# OpenSprinkler_v14_smt.net
KiCad netlist of a schematic drawn in EAGLE
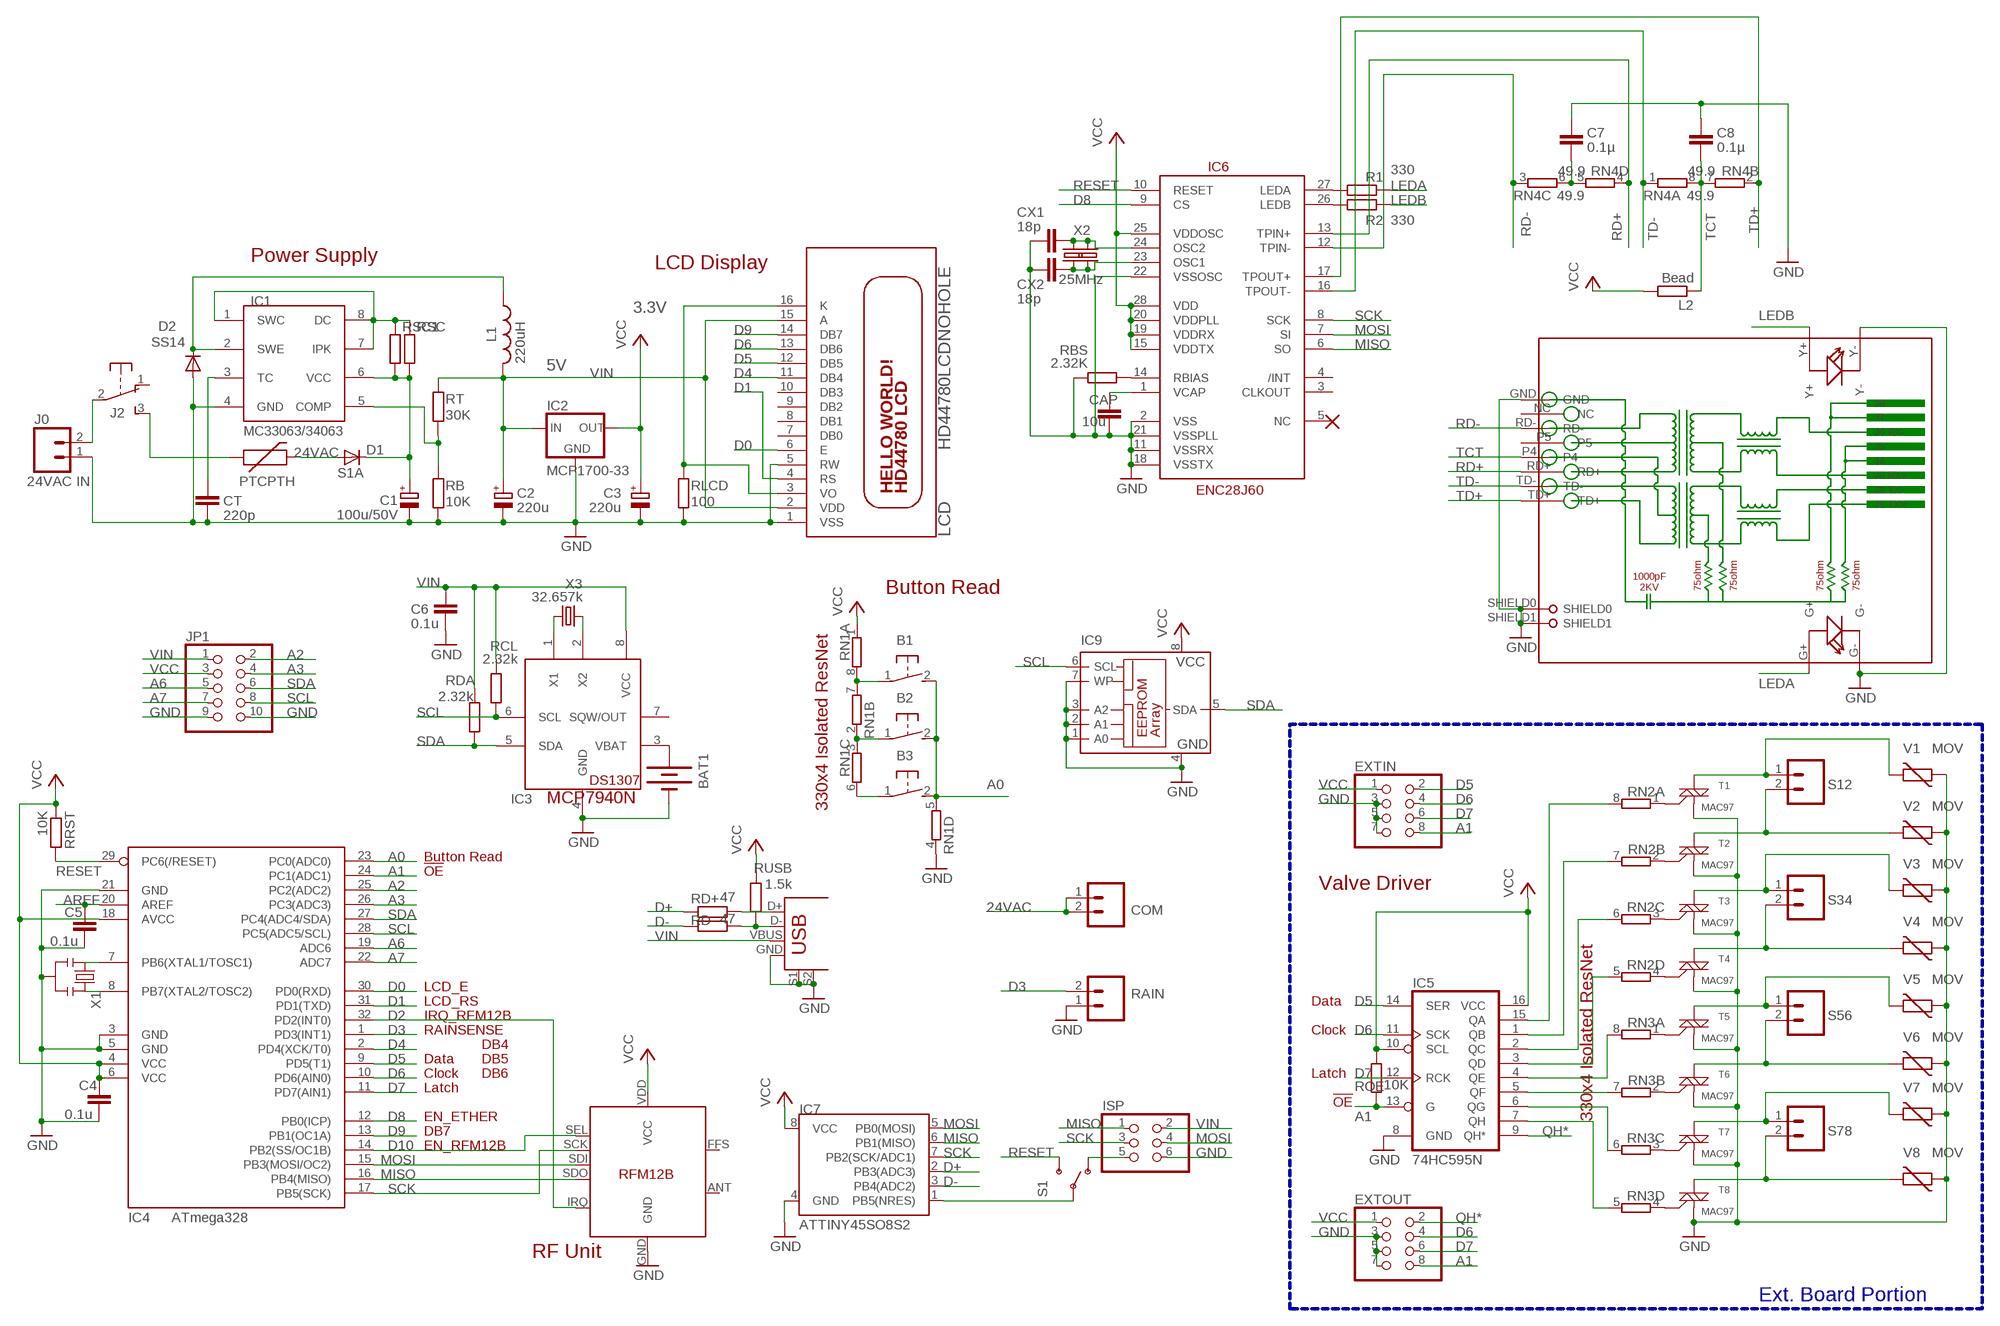
[diagram p0: schematic, sheet 1]

(export (version "E")
  (design (tool "Eeschema 10.0.6"))
  (components
    (comp (ref "B1")
      (value "31-XX")
      (footprint "eagle-import:B3F-31XX")
      (libsource (lib "eagle-import") (part "31-XX"))
    )
    (comp (ref "B2")
      (value "31-XX")
      (footprint "eagle-import:B3F-31XX")
      (libsource (lib "eagle-import") (part "31-XX"))
    )
    (comp (ref "B3")
      (value "31-XX")
      (footprint "eagle-import:B3F-31XX")
      (libsource (lib "eagle-import") (part "31-XX"))
    )
    (comp (ref "BAT1")
      (value "BATTERY12PTH")
      (footprint "eagle-import:BATTCON_12MM_PTH")
      (libsource (lib "eagle-import") (part "BATTERY12PTH"))
    )
    (comp (ref "C1")
      (value "100u/50V")
      (footprint "eagle-import:E3,5-8")
      (libsource (lib "eagle-import") (part "CPOL-EUE3.5-8"))
    )
    (comp (ref "C2")
      (value "220u")
      (footprint "eagle-import:E2-5")
      (libsource (lib "eagle-import") (part "CPOL-EUE2-5"))
    )
    (comp (ref "C3")
      (value "220u")
      (footprint "eagle-import:E2-5")
      (libsource (lib "eagle-import") (part "CPOL-EUE2-5"))
    )
    (comp (ref "C4")
      (value "0.1u")
      (footprint "eagle-import:C0805")
      (libsource (lib "eagle-import") (part "C-EUC0805"))
    )
    (comp (ref "C5")
      (value "0.1u")
      (footprint "eagle-import:C0805")
      (libsource (lib "eagle-import") (part "C-EUC0805"))
    )
    (comp (ref "C6")
      (value "0.1u")
      (footprint "eagle-import:C0805")
      (libsource (lib "eagle-import") (part "C-EUC0805"))
    )
    (comp (ref "C7")
      (value "0.1µ")
      (footprint "eagle-import:C0805")
      (libsource (lib "eagle-import") (part "resistor_C-EUC0805"))
    )
    (comp (ref "C8")
      (value "0.1µ")
      (footprint "eagle-import:C0805")
      (libsource (lib "eagle-import") (part "resistor_C-EUC0805"))
    )
    (comp (ref "CAP")
      (value "10u")
      (footprint "eagle-import:C0805")
      (libsource (lib "eagle-import") (part "resistor_C-EUC0805"))
    )
    (comp (ref "COM")
      (value "M025MM")
      (footprint "eagle-import:SCREWTERMINAL-5MM-2")
      (libsource (lib "eagle-import") (part "M025MM"))
    )
    (comp (ref "CT")
      (value "220p")
      (footprint "eagle-import:C0805")
      (libsource (lib "eagle-import") (part "C-EUC0805"))
    )
    (comp (ref "CX1")
      (value "18p")
      (footprint "eagle-import:C0805")
      (libsource (lib "eagle-import") (part "resistor_C-EUC0805"))
    )
    (comp (ref "CX2")
      (value "18p")
      (footprint "eagle-import:C0805")
      (libsource (lib "eagle-import") (part "resistor_C-EUC0805"))
    )
    (comp (ref "D1")
      (value "S1A")
      (footprint "eagle-import:DO214AC")
      (libsource (lib "eagle-import") (part "DIODE-DO214AC"))
    )
    (comp (ref "D2")
      (value "SS14")
      (footprint "eagle-import:DO214AC")
      (libsource (lib "eagle-import") (part "DIODE-DO214AC"))
    )
    (comp (ref "EXTIN")
      (value "PINHD-2X4")
      (footprint "eagle-import:2X04")
      (libsource (lib "eagle-import") (part "PINHD-2X4"))
    )
    (comp (ref "EXTOUT")
      (value "PINHD-2X4")
      (footprint "eagle-import:2X04")
      (libsource (lib "eagle-import") (part "PINHD-2X4"))
    )
    (comp (ref "IC1")
      (value "MC33063/MC34063D")
      (footprint "eagle-import:SO08")
      (libsource (lib "eagle-import") (part "MC33063/MC34063D"))
    )
    (comp (ref "IC2")
      (value "MCP1700-33")
      (footprint "eagle-import:SOT23")
      (libsource (lib "eagle-import") (part "MCP1700SOT233"))
    )
    (comp (ref "IC3")
      (value "MCP7940N")
      (footprint "eagle-import:SO08")
      (libsource (lib "eagle-import") (part "DS1307SOIC"))
    )
    (comp (ref "IC4")
      (value "ATmega328")
      (footprint "eagle-import:TQFP32-08")
      (fields (field (name "MPN") "ATMEGA8-16AU"))
      (libsource (lib "eagle-import") (part "MEGA8-AI"))
    )
    (comp (ref "IC5")
      (value "74HC595N")
      (footprint "eagle-import:SO16")
      (libsource (lib "eagle-import") (part "74595DLS"))
    )
    (comp (ref "IC6")
      (value "ENC28J60")
      (footprint "eagle-import:SOIC28WLONG")
      (libsource (lib "eagle-import") (part "ENC28J60SO28LONG"))
    )
    (comp (ref "IC7")
      (value "ATTINY45SO8S2")
      (footprint "eagle-import:SO8S2")
      (libsource (lib "eagle-import") (part "ATTINY45SO8S2"))
    )
    (comp (ref "IC8")
      (value "RFM12B")
      (footprint "eagle-import:RFM12B")
      (libsource (lib "eagle-import") (part "RFM12B"))
    )
    (comp (ref "IC9")
      (value "24AA128SN")
      (footprint "eagle-import:SO-08")
      (libsource (lib "eagle-import") (part "24SNAA128"))
    )
    (comp (ref "ISP")
      (value "PINHD-2X3")
      (footprint "eagle-import:2X03")
      (libsource (lib "eagle-import") (part "PINHD-2X3"))
    )
    (comp (ref "J0")
      (value "24VAC IN")
      (footprint "eagle-import:SCREWTERMINAL-5MM-2")
      (libsource (lib "eagle-import") (part "M025MM"))
    )
    (comp (ref "J2")
      (value "EG1206")
      (footprint "eagle-import:EG1206")
      (libsource (lib "eagle-import") (part "EG1206"))
    )
    (comp (ref "JP1")
      (value "PINHD-2X5")
      (footprint "eagle-import:2X05")
      (libsource (lib "eagle-import") (part "PINHD-2X5"))
    )
    (comp (ref "L1")
      (value "220uH")
      (footprint "eagle-import:6000-XXXX-RC")
      (libsource (lib "eagle-import") (part "L-US6000-XXX-RC"))
    )
    (comp (ref "L2")
      (value "Bead")
      (footprint "eagle-import:R0805")
      (libsource (lib "eagle-import") (part "R-EU_R0805"))
    )
    (comp (ref "LCD")
      (value "HD44780LCDNOHOLE")
      (footprint "eagle-import:LCD1602A")
      (libsource (lib "eagle-import") (part "HD44780LCDNOHOLE"))
    )
    (comp (ref "PTC")
      (value "PTCPTH")
      (footprint "eagle-import:PTC")
      (libsource (lib "eagle-import") (part "PTCPTH"))
    )
    (comp (ref "R1")
      (value "330")
      (footprint "eagle-import:R0805")
      (libsource (lib "eagle-import") (part "R-EU_R0805"))
    )
    (comp (ref "R2")
      (value "330")
      (footprint "eagle-import:R0805")
      (libsource (lib "eagle-import") (part "R-EU_R0805"))
    )
    (comp (ref "RAIN")
      (value "M025MM")
      (footprint "eagle-import:SCREWTERMINAL-5MM-2")
      (libsource (lib "eagle-import") (part "M025MM"))
    )
    (comp (ref "RB")
      (value "10K")
      (footprint "eagle-import:R0805")
      (libsource (lib "eagle-import") (part "R-EU_R0805"))
    )
    (comp (ref "RBS")
      (value "2.32K")
      (footprint "eagle-import:R0805")
      (libsource (lib "eagle-import") (part "R-EU_R0805"))
    )
    (comp (ref "RCL")
      (value "2.32k")
      (footprint "eagle-import:R0805")
      (libsource (lib "eagle-import") (part "R-EU_R0805"))
    )
    (comp (ref "RD+")
      (value "47")
      (footprint "eagle-import:R0805")
      (libsource (lib "eagle-import") (part "R-EU_R0805"))
    )
    (comp (ref "RD-")
      (value "47")
      (footprint "eagle-import:R0805")
      (libsource (lib "eagle-import") (part "R-EU_R0805"))
    )
    (comp (ref "RDA")
      (value "2.32k")
      (footprint "eagle-import:R0805")
      (libsource (lib "eagle-import") (part "R-EU_R0805"))
    )
    (comp (ref "RJ1")
      (value "HR911105A")
      (footprint "eagle-import:HR911105A")
      (libsource (lib "eagle-import") (part "HR911105A"))
    )
    (comp (ref "RLCD")
      (value "100")
      (footprint "eagle-import:R0805")
      (libsource (lib "eagle-import") (part "R-EU_R0805"))
    )
    (comp (ref "RN1")
      (value "4R-NEXBV8V")
      (footprint "eagle-import:EXBV8V")
      (libsource (lib "eagle-import") (part "4R-NEXBV8V"))
    )
    (comp (ref "RN2")
      (value "4R-NEXBV8V")
      (footprint "eagle-import:EXBV8V")
      (libsource (lib "eagle-import") (part "4R-NEXBV8V"))
    )
    (comp (ref "RN3")
      (value "4R-NEXBV8V")
      (footprint "eagle-import:EXBV8V")
      (libsource (lib "eagle-import") (part "4R-NEXBV8V"))
    )
    (comp (ref "RN4")
      (value "49.9")
      (footprint "eagle-import:EXBV8V")
      (libsource (lib "eagle-import") (part "4R-NEXBV8V"))
    )
    (comp (ref "ROE")
      (value "10K")
      (footprint "eagle-import:R0805")
      (libsource (lib "eagle-import") (part "R-EU_R0805"))
    )
    (comp (ref "RRST")
      (value "10K")
      (footprint "eagle-import:R0805")
      (libsource (lib "eagle-import") (part "R-EU_R0805"))
    )
    (comp (ref "RSC")
      (value "1.0")
      (footprint "eagle-import:R0805")
      (libsource (lib "eagle-import") (part "R-EU_R0805"))
    )
    (comp (ref "RSC1")
      (value "1.0")
      (footprint "eagle-import:R0805")
      (libsource (lib "eagle-import") (part "R-EU_R0805"))
    )
    (comp (ref "RT")
      (value "30K")
      (footprint "eagle-import:R0805")
      (libsource (lib "eagle-import") (part "R-EU_R0805"))
    )
    (comp (ref "RUSB")
      (value "1.5k")
      (footprint "eagle-import:R0805")
      (libsource (lib "eagle-import") (part "R-EU_R0805"))
    )
    (comp (ref "S1")
      (value "SWITCH-SPSTSMD2")
      (footprint "eagle-import:SWITCH-SPDT-SMD")
      (libsource (lib "eagle-import") (part "SWITCH-SPSTSMD2"))
    )
    (comp (ref "S12")
      (value "M025MM")
      (footprint "eagle-import:SCREWTERMINAL-5MM-2")
      (libsource (lib "eagle-import") (part "M025MM"))
    )
    (comp (ref "S34")
      (value "M025MM")
      (footprint "eagle-import:SCREWTERMINAL-5MM-2")
      (libsource (lib "eagle-import") (part "M025MM"))
    )
    (comp (ref "S56")
      (value "M025MM")
      (footprint "eagle-import:SCREWTERMINAL-5MM-2")
      (libsource (lib "eagle-import") (part "M025MM"))
    )
    (comp (ref "S78")
      (value "M025MM")
      (footprint "eagle-import:SCREWTERMINAL-5MM-2")
      (libsource (lib "eagle-import") (part "M025MM"))
    )
    (comp (ref "T1")
      (value "MAC97")
      (footprint "eagle-import:SOT223")
      (libsource (lib "eagle-import") (part "MAC97SOT223"))
    )
    (comp (ref "T2")
      (value "MAC97")
      (footprint "eagle-import:SOT223")
      (libsource (lib "eagle-import") (part "MAC97SOT223"))
    )
    (comp (ref "T3")
      (value "MAC97")
      (footprint "eagle-import:SOT223")
      (libsource (lib "eagle-import") (part "MAC97SOT223"))
    )
    (comp (ref "T4")
      (value "MAC97")
      (footprint "eagle-import:SOT223")
      (libsource (lib "eagle-import") (part "MAC97SOT223"))
    )
    (comp (ref "T5")
      (value "MAC97")
      (footprint "eagle-import:SOT223")
      (libsource (lib "eagle-import") (part "MAC97SOT223"))
    )
    (comp (ref "T6")
      (value "MAC97")
      (footprint "eagle-import:SOT223")
      (libsource (lib "eagle-import") (part "MAC97SOT223"))
    )
    (comp (ref "T7")
      (value "MAC97")
      (footprint "eagle-import:SOT223")
      (libsource (lib "eagle-import") (part "MAC97SOT223"))
    )
    (comp (ref "T8")
      (value "MAC97")
      (footprint "eagle-import:SOT223")
      (libsource (lib "eagle-import") (part "MAC97SOT223"))
    )
    (comp (ref "USB")
      (value "USB+SHIELD")
      (footprint "eagle-import:USB-B-PTH")
      (libsource (lib "eagle-import") (part "USB+SHIELD"))
    )
    (comp (ref "V1")
      (value "MOV")
      (footprint "eagle-import:R-5")
      (libsource (lib "eagle-import") (part "VARISTOR-5"))
    )
    (comp (ref "V2")
      (value "MOV")
      (footprint "eagle-import:R-5")
      (libsource (lib "eagle-import") (part "VARISTOR-5"))
    )
    (comp (ref "V3")
      (value "MOV")
      (footprint "eagle-import:R-5")
      (libsource (lib "eagle-import") (part "VARISTOR-5"))
    )
    (comp (ref "V4")
      (value "MOV")
      (footprint "eagle-import:R-5")
      (libsource (lib "eagle-import") (part "VARISTOR-5"))
    )
    (comp (ref "V5")
      (value "MOV")
      (footprint "eagle-import:R-5")
      (libsource (lib "eagle-import") (part "VARISTOR-5"))
    )
    (comp (ref "V6")
      (value "MOV")
      (footprint "eagle-import:R-5")
      (libsource (lib "eagle-import") (part "VARISTOR-5"))
    )
    (comp (ref "V7")
      (value "MOV")
      (footprint "eagle-import:R-5")
      (libsource (lib "eagle-import") (part "VARISTOR-5"))
    )
    (comp (ref "V8")
      (value "MOV")
      (footprint "eagle-import:R-5")
      (libsource (lib "eagle-import") (part "VARISTOR-5"))
    )
    (comp (ref "X1")
      (value "RESONATORSMD")
      (footprint "eagle-import:RESONATOR-SMD")
      (libsource (lib "eagle-import") (part "RESONATORSMD"))
    )
    (comp (ref "X2")
      (value "25MHz")
      (footprint "eagle-import:HC49UP")
      (libsource (lib "eagle-import") (part "CRYSTALSMD"))
    )
    (comp (ref "X2A")
      (value "25MHz")
      (footprint "eagle-import:HC49US")
      (libsource (lib "eagle-import") (part "CRYSTALHC49US"))
    )
    (comp (ref "X3")
      (value "32.657k")
      (footprint "eagle-import:TC26H")
      (libsource (lib "eagle-import") (part "crystal_CRYSTALTC26H"))
    )
  )
  (nets
    (net (code "1") (name "/24VAC") (class "Default")
      (node (ref "COM") (pin "1") (pinfunction "1_1") (pintype "passive"))
      (node (ref "COM") (pin "2") (pinfunction "2_2") (pintype "passive"))
      (node (ref "D1") (pin "A") (pinfunction "A_A") (pintype "passive"))
      (node (ref "PTC") (pin "P$2") (pinfunction "2_P$2") (pintype "bidirectional"))
    )
    (net (code "2") (name "/A0") (class "Default")
      (node (ref "B1") (pin "2") (pinfunction "S_2") (pintype "passive"))
      (node (ref "B2") (pin "2") (pinfunction "S_2") (pintype "passive"))
      (node (ref "B3") (pin "2") (pinfunction "S_2") (pintype "passive"))
      (node (ref "IC4") (pin "23") (pinfunction "PC0(ADC0)_23") (pintype "bidirectional"))
      (node (ref "RN1") (pin "5") (pinfunction "2_5") (pintype "passive"))
    )
    (net (code "3") (name "/A1") (class "Default")
      (node (ref "EXTIN") (pin "8") (pinfunction "8_8") (pintype "passive"))
      (node (ref "EXTOUT") (pin "8") (pinfunction "8_8") (pintype "passive"))
      (node (ref "IC4") (pin "24") (pinfunction "PC1(ADC1)_24") (pintype "bidirectional"))
      (node (ref "IC5") (pin "13") (pinfunction "G_13") (pintype "input"))
      (node (ref "ROE") (pin "1") (pinfunction "1_1") (pintype "passive"))
    )
    (net (code "4") (name "/A2") (class "Default")
      (node (ref "IC4") (pin "25") (pinfunction "PC2(ADC2)_25") (pintype "bidirectional"))
      (node (ref "JP1") (pin "2") (pinfunction "2_2") (pintype "passive"))
    )
    (net (code "5") (name "/A3") (class "Default")
      (node (ref "IC4") (pin "26") (pinfunction "PC3(ADC3)_26") (pintype "bidirectional"))
      (node (ref "JP1") (pin "4") (pinfunction "4_4") (pintype "passive"))
    )
    (net (code "6") (name "/A6") (class "Default")
      (node (ref "IC4") (pin "19") (pinfunction "ADC6_19") (pintype "bidirectional"))
      (node (ref "JP1") (pin "5") (pinfunction "5_5") (pintype "passive"))
    )
    (net (code "7") (name "/A7") (class "Default")
      (node (ref "IC4") (pin "22") (pinfunction "ADC7_22") (pintype "bidirectional"))
      (node (ref "JP1") (pin "7") (pinfunction "7_7") (pintype "passive"))
    )
    (net (code "8") (name "/AREF") (class "Default")
      (node (ref "C5") (pin "1") (pinfunction "1_1") (pintype "passive"))
      (node (ref "IC4") (pin "20") (pinfunction "AREF_20") (pintype "passive"))
    )
    (net (code "9") (name "/D+") (class "Default")
      (node (ref "IC7") (pin "2") (pinfunction "PB3(ADC3)_2") (pintype "bidirectional"))
      (node (ref "RD+") (pin "1") (pinfunction "1_1") (pintype "passive"))
    )
    (net (code "10") (name "/D-") (class "Default")
      (node (ref "IC7") (pin "3") (pinfunction "PB4(ADC2)_3") (pintype "bidirectional"))
      (node (ref "RD-") (pin "1") (pinfunction "1_1") (pintype "passive"))
    )
    (net (code "11") (name "/D0") (class "Default")
      (node (ref "IC4") (pin "30") (pinfunction "PD0(RXD)_30") (pintype "bidirectional"))
      (node (ref "LCD") (pin "6") (pinfunction "E_6") (pintype "input"))
    )
    (net (code "12") (name "/D1") (class "Default")
      (node (ref "IC4") (pin "31") (pinfunction "PD1(TXD)_31") (pintype "bidirectional"))
      (node (ref "LCD") (pin "4") (pinfunction "RS_4") (pintype "input"))
    )
    (net (code "13") (name "/D2") (class "Default")
      (node (ref "IC4") (pin "32") (pinfunction "PD2(INT0)_32") (pintype "bidirectional"))
      (node (ref "IC8") (pin "IRQ") (pinfunction "IRQ_IRQ") (pintype "open_collector"))
    )
    (net (code "14") (name "/D3") (class "Default")
      (node (ref "IC4") (pin "1") (pinfunction "PD3(INT1)_1") (pintype "bidirectional"))
      (node (ref "RAIN") (pin "2") (pinfunction "2_2") (pintype "passive"))
    )
    (net (code "15") (name "/D4") (class "Default")
      (node (ref "IC4") (pin "2") (pinfunction "PD4(XCK/T0)_2") (pintype "bidirectional"))
      (node (ref "LCD") (pin "11") (pinfunction "DB4_11") (pintype "bidirectional"))
    )
    (net (code "16") (name "/D5") (class "Default")
      (node (ref "EXTIN") (pin "2") (pinfunction "2_2") (pintype "passive"))
      (node (ref "IC4") (pin "9") (pinfunction "PD5(T1)_9") (pintype "bidirectional"))
      (node (ref "IC5") (pin "14") (pinfunction "SER_14") (pintype "input"))
      (node (ref "LCD") (pin "12") (pinfunction "DB5_12") (pintype "bidirectional"))
    )
    (net (code "17") (name "/D6") (class "Default")
      (node (ref "EXTIN") (pin "4") (pinfunction "4_4") (pintype "passive"))
      (node (ref "EXTOUT") (pin "4") (pinfunction "4_4") (pintype "passive"))
      (node (ref "IC4") (pin "10") (pinfunction "PD6(AIN0)_10") (pintype "bidirectional"))
      (node (ref "IC5") (pin "11") (pinfunction "SCK_11") (pintype "input"))
      (node (ref "LCD") (pin "13") (pinfunction "DB6_13") (pintype "bidirectional"))
    )
    (net (code "18") (name "/D7") (class "Default")
      (node (ref "EXTIN") (pin "6") (pinfunction "6_6") (pintype "passive"))
      (node (ref "EXTOUT") (pin "6") (pinfunction "6_6") (pintype "passive"))
      (node (ref "IC4") (pin "11") (pinfunction "PD7(AIN1)_11") (pintype "bidirectional"))
      (node (ref "IC5") (pin "12") (pinfunction "RCK_12") (pintype "input"))
    )
    (net (code "19") (name "/D8") (class "Default")
      (node (ref "IC4") (pin "12") (pinfunction "PB0(ICP)_12") (pintype "bidirectional"))
      (node (ref "IC6") (pin "9") (pinfunction "CS_9") (pintype "bidirectional"))
    )
    (net (code "20") (name "/D9") (class "Default")
      (node (ref "IC4") (pin "13") (pinfunction "PB1(OC1A)_13") (pintype "bidirectional"))
      (node (ref "LCD") (pin "14") (pinfunction "DB7_14") (pintype "bidirectional"))
    )
    (net (code "21") (name "/D10") (class "Default")
      (node (ref "IC4") (pin "14") (pinfunction "PB2(SS/OC1B)_14") (pintype "bidirectional"))
      (node (ref "IC8") (pin "SEL") (pinfunction "SEL_SEL") (pintype "input"))
    )
    (net (code "22") (name "/LEDA") (class "Default")
      (node (ref "R1") (pin "2") (pinfunction "2_2") (pintype "passive"))
      (node (ref "RJ1") (pin "G+") (pinfunction "G+_G+") (pintype "bidirectional"))
    )
    (net (code "23") (name "/LEDB") (class "Default")
      (node (ref "R2") (pin "2") (pinfunction "2_2") (pintype "passive"))
      (node (ref "RJ1") (pin "Y+") (pinfunction "Y+_Y+") (pintype "bidirectional"))
    )
    (net (code "24") (name "/MISO") (class "Default")
      (node (ref "IC4") (pin "16") (pinfunction "PB4(MISO)_16") (pintype "bidirectional"))
      (node (ref "IC6") (pin "6") (pinfunction "SO_6") (pintype "bidirectional"))
      (node (ref "IC7") (pin "6") (pinfunction "PB1(MISO)_6") (pintype "bidirectional"))
      (node (ref "IC8") (pin "SDO") (pinfunction "SDO_SDO") (pintype "output"))
      (node (ref "ISP") (pin "1") (pinfunction "1_1") (pintype "passive"))
    )
    (net (code "25") (name "/MOSI") (class "Default")
      (node (ref "IC4") (pin "15") (pinfunction "PB3(MOSI/OC2)_15") (pintype "bidirectional"))
      (node (ref "IC6") (pin "7") (pinfunction "SI_7") (pintype "bidirectional"))
      (node (ref "IC7") (pin "5") (pinfunction "PB0(MOSI)_5") (pintype "bidirectional"))
      (node (ref "IC8") (pin "SDI") (pinfunction "SDI_SDI") (pintype "input"))
      (node (ref "ISP") (pin "4") (pinfunction "4_4") (pintype "passive"))
    )
    (net (code "26") (name "/QH*") (class "Default")
      (node (ref "EXTOUT") (pin "2") (pinfunction "2_2") (pintype "passive"))
      (node (ref "IC5") (pin "9") (pinfunction "QH*_9") (pintype "tri_state"))
    )
    (net (code "27") (name "/RD+") (class "Default")
      (node (ref "IC6") (pin "13") (pinfunction "TPIN+_13") (pintype "bidirectional"))
      (node (ref "RJ1") (pin "RD+") (pinfunction "RD+_RD+") (pintype "bidirectional"))
      (node (ref "RN4") (pin "4") (pinfunction "1_4") (pintype "passive"))
    )
    (net (code "28") (name "/RD-") (class "Default")
      (node (ref "IC6") (pin "12") (pinfunction "TPIN-_12") (pintype "bidirectional"))
      (node (ref "RJ1") (pin "RD-") (pinfunction "RD-_RD-") (pintype "bidirectional"))
      (node (ref "RN4") (pin "3") (pinfunction "1_3") (pintype "passive"))
    )
    (net (code "29") (name "/RESET") (class "Default")
      (node (ref "IC4") (pin "29") (pinfunction "PC6(/RESET)_29") (pintype "bidirectional"))
      (node (ref "IC6") (pin "10") (pinfunction "RESET_10") (pintype "bidirectional"))
      (node (ref "RRST") (pin "2") (pinfunction "2_2") (pintype "passive"))
      (node (ref "S1") (pin "3") (pinfunction "S_3") (pintype "passive"))
    )
    (net (code "30") (name "/SCK") (class "Default")
      (node (ref "IC4") (pin "17") (pinfunction "PB5(SCK)_17") (pintype "bidirectional"))
      (node (ref "IC6") (pin "8") (pinfunction "SCK_8") (pintype "bidirectional"))
      (node (ref "IC7") (pin "7") (pinfunction "PB2(SCK/ADC1)_7") (pintype "bidirectional"))
      (node (ref "IC8") (pin "SCK") (pinfunction "SCK_SCK") (pintype "input"))
      (node (ref "ISP") (pin "3") (pinfunction "3_3") (pintype "passive"))
    )
    (net (code "31") (name "/SCL") (class "Default")
      (node (ref "IC3") (pin "6") (pinfunction "SCL_6") (pintype "bidirectional"))
      (node (ref "IC4") (pin "28") (pinfunction "PC5(ADC5/SCL)_28") (pintype "bidirectional"))
      (node (ref "IC9") (pin "6") (pinfunction "SCL_6") (pintype "input"))
      (node (ref "JP1") (pin "8") (pinfunction "8_8") (pintype "passive"))
      (node (ref "RCL") (pin "2") (pinfunction "2_2") (pintype "passive"))
    )
    (net (code "32") (name "/SDA") (class "Default")
      (node (ref "IC3") (pin "5") (pinfunction "SDA_5") (pintype "bidirectional"))
      (node (ref "IC4") (pin "27") (pinfunction "PC4(ADC4/SDA)_27") (pintype "bidirectional"))
      (node (ref "IC9") (pin "5") (pinfunction "SDA_5") (pintype "bidirectional"))
      (node (ref "JP1") (pin "6") (pinfunction "6_6") (pintype "passive"))
      (node (ref "RDA") (pin "2") (pinfunction "2_2") (pintype "passive"))
    )
    (net (code "33") (name "/TCT") (class "Default")
      (node (ref "C8") (pin "2") (pinfunction "2_2") (pintype "passive"))
      (node (ref "L2") (pin "1") (pinfunction "1_1") (pintype "passive"))
      (node (ref "RJ1") (pin "P4") (pinfunction "P4_P4") (pintype "bidirectional"))
      (node (ref "RN4") (pin "7") (pinfunction "2_7") (pintype "passive"))
      (node (ref "RN4") (pin "8") (pinfunction "2_8") (pintype "passive"))
    )
    (net (code "34") (name "/TD+") (class "Default")
      (node (ref "IC6") (pin "17") (pinfunction "TPOUT+_17") (pintype "bidirectional"))
      (node (ref "RJ1") (pin "TD+") (pinfunction "TD+_TD+") (pintype "bidirectional"))
      (node (ref "RN4") (pin "2") (pinfunction "1_2") (pintype "passive"))
    )
    (net (code "35") (name "/TD-") (class "Default")
      (node (ref "IC6") (pin "16") (pinfunction "TPOUT-_16") (pintype "bidirectional"))
      (node (ref "RJ1") (pin "TD-") (pinfunction "TD-_TD-") (pintype "bidirectional"))
      (node (ref "RN4") (pin "1") (pinfunction "1_1") (pintype "passive"))
    )
    (net (code "36") (name "/VIN") (class "Default")
      (node (ref "C2") (pin "+") (pinfunction "+_+") (pintype "passive"))
      (node (ref "C6") (pin "1") (pinfunction "1_1") (pintype "passive"))
      (node (ref "IC2") (pin "3") (pinfunction "IN_3") (pintype "input"))
      (node (ref "IC3") (pin "8") (pinfunction "VCC_8") (pintype "power_in"))
      (node (ref "ISP") (pin "2") (pinfunction "2_2") (pintype "passive"))
      (node (ref "JP1") (pin "1") (pinfunction "1_1") (pintype "passive"))
      (node (ref "L1") (pin "2") (pinfunction "2_2") (pintype "passive"))
      (node (ref "LCD") (pin "15") (pinfunction "A_15") (pintype "input"))
      (node (ref "LCD") (pin "2") (pinfunction "VDD_2") (pintype "power_in"))
      (node (ref "RCL") (pin "1") (pinfunction "1_1") (pintype "passive"))
      (node (ref "RDA") (pin "1") (pinfunction "1_1") (pintype "passive"))
      (node (ref "RT") (pin "1") (pinfunction "1_1") (pintype "passive"))
      (node (ref "USB") (pin "VBUS") (pinfunction "VBUS_VBUS") (pintype "bidirectional"))
    )
    (net (code "37") (name "GND") (class "Default")
      (node (ref "BAT1") (pin "GND") (pinfunction "-_GND") (pintype "power_in"))
      (node (ref "C1") (pin "-") (pinfunction "-_-") (pintype "passive"))
      (node (ref "C2") (pin "-") (pinfunction "-_-") (pintype "passive"))
      (node (ref "C3") (pin "-") (pinfunction "-_-") (pintype "passive"))
      (node (ref "C4") (pin "2") (pinfunction "2_2") (pintype "passive"))
      (node (ref "C5") (pin "2") (pinfunction "2_2") (pintype "passive"))
      (node (ref "C6") (pin "2") (pinfunction "2_2") (pintype "passive"))
      (node (ref "C7") (pin "1") (pinfunction "1_1") (pintype "passive"))
      (node (ref "C8") (pin "1") (pinfunction "1_1") (pintype "passive"))
      (node (ref "CAP") (pin "2") (pinfunction "2_2") (pintype "passive"))
      (node (ref "CT") (pin "2") (pinfunction "2_2") (pintype "passive"))
      (node (ref "CX1") (pin "2") (pinfunction "2_2") (pintype "passive"))
      (node (ref "CX2") (pin "2") (pinfunction "2_2") (pintype "passive"))
      (node (ref "D2") (pin "A") (pinfunction "A_A") (pintype "passive"))
      (node (ref "EXTIN") (pin "3") (pinfunction "3_3") (pintype "passive"))
      (node (ref "EXTIN") (pin "5") (pinfunction "5_5") (pintype "passive"))
      (node (ref "EXTIN") (pin "7") (pinfunction "7_7") (pintype "passive"))
      (node (ref "EXTOUT") (pin "3") (pinfunction "3_3") (pintype "passive"))
      (node (ref "EXTOUT") (pin "5") (pinfunction "5_5") (pintype "passive"))
      (node (ref "EXTOUT") (pin "7") (pinfunction "7_7") (pintype "passive"))
      (node (ref "IC1") (pin "4") (pinfunction "GND_4") (pintype "power_in"))
      (node (ref "IC2") (pin "1") (pinfunction "GND_1") (pintype "input"))
      (node (ref "IC3") (pin "4") (pinfunction "GND_4") (pintype "power_in"))
      (node (ref "IC4") (pin "21") (pinfunction "GND_21") (pintype "power_in"))
      (node (ref "IC4") (pin "3") (pinfunction "GND_3") (pintype "power_in"))
      (node (ref "IC4") (pin "5") (pinfunction "GND_5") (pintype "power_in"))
      (node (ref "IC5") (pin "8") (pinfunction "GND_8") (pintype "power_in"))
      (node (ref "IC6") (pin "11") (pinfunction "VSSRX_11") (pintype "bidirectional"))
      (node (ref "IC6") (pin "18") (pinfunction "VSSTX_18") (pintype "bidirectional"))
      (node (ref "IC6") (pin "2") (pinfunction "VSS_2") (pintype "bidirectional"))
      (node (ref "IC6") (pin "21") (pinfunction "VSSPLL_21") (pintype "bidirectional"))
      (node (ref "IC6") (pin "22") (pinfunction "VSSOSC_22") (pintype "bidirectional"))
      (node (ref "IC7") (pin "4") (pinfunction "GND_4") (pintype "bidirectional"))
      (node (ref "IC8") (pin "GND") (pinfunction "GND_GND") (pintype "power_in"))
      (node (ref "IC9") (pin "1") (pinfunction "A0_1") (pintype "input"))
      (node (ref "IC9") (pin "2") (pinfunction "A1_2") (pintype "input"))
      (node (ref "IC9") (pin "3") (pinfunction "A2_3") (pintype "input"))
      (node (ref "IC9") (pin "4") (pinfunction "GND_4") (pintype "power_in"))
      (node (ref "IC9") (pin "7") (pinfunction "WP_7") (pintype "input"))
      (node (ref "ISP") (pin "6") (pinfunction "6_6") (pintype "passive"))
      (node (ref "J0") (pin "1") (pinfunction "1_1") (pintype "passive"))
      (node (ref "JP1") (pin "10") (pinfunction "10_10") (pintype "passive"))
      (node (ref "JP1") (pin "9") (pinfunction "9_9") (pintype "passive"))
      (node (ref "LCD") (pin "1") (pinfunction "VSS_1") (pintype "power_in"))
      (node (ref "LCD") (pin "5") (pinfunction "RW_5") (pintype "input"))
      (node (ref "RAIN") (pin "1") (pinfunction "1_1") (pintype "passive"))
      (node (ref "RB") (pin "2") (pinfunction "2_2") (pintype "passive"))
      (node (ref "RBS") (pin "1") (pinfunction "1_1") (pintype "passive"))
      (node (ref "RJ1") (pin "G-") (pinfunction "G-_G-") (pintype "bidirectional"))
      (node (ref "RJ1") (pin "GND") (pinfunction "GND_GND") (pintype "bidirectional"))
      (node (ref "RJ1") (pin "SHIELD0") (pinfunction "SHIELD0_SHIELD0") (pintype "bidirectional"))
      (node (ref "RJ1") (pin "SHIELD1") (pinfunction "SHIELD1_SHIELD1") (pintype "bidirectional"))
      (node (ref "RJ1") (pin "Y-") (pinfunction "Y-_Y-") (pintype "bidirectional"))
      (node (ref "RLCD") (pin "2") (pinfunction "2_2") (pintype "passive"))
      (node (ref "RN1") (pin "4") (pinfunction "1_4") (pintype "passive"))
      (node (ref "T1") (pin "1") (pinfunction "M1_1") (pintype "bidirectional"))
      (node (ref "T2") (pin "1") (pinfunction "M1_1") (pintype "bidirectional"))
      (node (ref "T3") (pin "1") (pinfunction "M1_1") (pintype "bidirectional"))
      (node (ref "T4") (pin "1") (pinfunction "M1_1") (pintype "bidirectional"))
      (node (ref "T5") (pin "1") (pinfunction "M1_1") (pintype "bidirectional"))
      (node (ref "T6") (pin "1") (pinfunction "M1_1") (pintype "bidirectional"))
      (node (ref "T7") (pin "1") (pinfunction "M1_1") (pintype "bidirectional"))
      (node (ref "T8") (pin "1") (pinfunction "M1_1") (pintype "bidirectional"))
      (node (ref "USB") (pin "GND") (pinfunction "GND_GND") (pintype "bidirectional"))
      (node (ref "USB") (pin "S1") (pinfunction "P$1_S1") (pintype "bidirectional"))
      (node (ref "USB") (pin "S2") (pinfunction "P$2_S2") (pintype "bidirectional"))
      (node (ref "V1") (pin "1") (pinfunction "1_1") (pintype "passive"))
      (node (ref "V2") (pin "1") (pinfunction "1_1") (pintype "passive"))
      (node (ref "V3") (pin "1") (pinfunction "1_1") (pintype "passive"))
      (node (ref "V4") (pin "1") (pinfunction "1_1") (pintype "passive"))
      (node (ref "V5") (pin "1") (pinfunction "1_1") (pintype "passive"))
      (node (ref "V6") (pin "1") (pinfunction "1_1") (pintype "passive"))
      (node (ref "V7") (pin "1") (pinfunction "1_1") (pintype "passive"))
      (node (ref "V8") (pin "1") (pinfunction "1_1") (pintype "passive"))
      (node (ref "X1") (pin "2") (pinfunction "2_2") (pintype "passive"))
    )
    (net (code "38") (name "Net-(B1-P)") (class "Default")
      (node (ref "B1") (pin "1") (pinfunction "P_1") (pintype "passive"))
      (node (ref "RN1") (pin "7") (pinfunction "2_7") (pintype "passive"))
      (node (ref "RN1") (pin "8") (pinfunction "2_8") (pintype "passive"))
    )
    (net (code "39") (name "Net-(B2-P)") (class "Default")
      (node (ref "B2") (pin "1") (pinfunction "P_1") (pintype "passive"))
      (node (ref "RN1") (pin "2") (pinfunction "1_2") (pintype "passive"))
      (node (ref "RN1") (pin "3") (pinfunction "1_3") (pintype "passive"))
    )
    (net (code "40") (name "Net-(B3-P)") (class "Default")
      (node (ref "B3") (pin "1") (pinfunction "P_1") (pintype "passive"))
      (node (ref "RN1") (pin "6") (pinfunction "2_6") (pintype "passive"))
    )
    (net (code "41") (name "Net-(BAT1-+)") (class "Default")
      (node (ref "BAT1") (pin "VCC@1") (pinfunction "+_VCC@1") (pintype "power_in"))
      (node (ref "IC3") (pin "3") (pinfunction "VBAT_3") (pintype "power_in"))
    )
    (net (code "42") (name "Net-(IC1-COMP)") (class "Default")
      (node (ref "IC1") (pin "5") (pinfunction "COMP_5") (pintype "input"))
      (node (ref "RB") (pin "1") (pinfunction "1_1") (pintype "passive"))
      (node (ref "RT") (pin "2") (pinfunction "2_2") (pintype "passive"))
    )
    (net (code "43") (name "Net-(IC1-DC)") (class "Default")
      (node (ref "IC1") (pin "1") (pinfunction "SWC_1") (pintype "input"))
      (node (ref "IC1") (pin "7") (pinfunction "IPK_7") (pintype "bidirectional"))
      (node (ref "IC1") (pin "8") (pinfunction "DC_8") (pintype "input"))
      (node (ref "RSC") (pin "1") (pinfunction "1_1") (pintype "passive"))
      (node (ref "RSC1") (pin "1") (pinfunction "1_1") (pintype "passive"))
    )
    (net (code "44") (name "Net-(IC1-SWE)") (class "Default")
      (node (ref "D2") (pin "C") (pinfunction "C_C") (pintype "passive"))
      (node (ref "IC1") (pin "2") (pinfunction "SWE_2") (pintype "input"))
      (node (ref "L1") (pin "1") (pinfunction "1_1") (pintype "passive"))
    )
    (net (code "45") (name "Net-(IC1-TC)") (class "Default")
      (node (ref "CT") (pin "1") (pinfunction "1_1") (pintype "passive"))
      (node (ref "IC1") (pin "3") (pinfunction "TC_3") (pintype "input"))
    )
    (net (code "46") (name "Net-(IC1-VCC)") (class "Default")
      (node (ref "C1") (pin "+") (pinfunction "+_+") (pintype "passive"))
      (node (ref "D1") (pin "C") (pinfunction "C_C") (pintype "passive"))
      (node (ref "IC1") (pin "6") (pinfunction "VCC_6") (pintype "power_in"))
      (node (ref "RSC") (pin "2") (pinfunction "2_2") (pintype "passive"))
      (node (ref "RSC1") (pin "2") (pinfunction "2_2") (pintype "passive"))
    )
    (net (code "47") (name "Net-(IC3-X1)") (class "Default")
      (node (ref "IC3") (pin "1") (pinfunction "X1_1") (pintype "passive"))
      (node (ref "X3") (pin "1") (pinfunction "1_1") (pintype "passive"))
    )
    (net (code "48") (name "Net-(IC3-X2)") (class "Default")
      (node (ref "IC3") (pin "2") (pinfunction "X2_2") (pintype "passive"))
      (node (ref "X3") (pin "2") (pinfunction "2_2") (pintype "passive"))
    )
    (net (code "49") (name "Net-(IC4-PB6(XTAL1{slash}TOSC1))") (class "Default")
      (node (ref "IC4") (pin "7") (pinfunction "PB6(XTAL1/TOSC1)_7") (pintype "bidirectional"))
      (node (ref "X1") (pin "1") (pinfunction "1_1") (pintype "passive"))
    )
    (net (code "50") (name "Net-(IC4-PB7(XTAL2{slash}TOSC2))") (class "Default")
      (node (ref "IC4") (pin "8") (pinfunction "PB7(XTAL2/TOSC2)_8") (pintype "bidirectional"))
      (node (ref "X1") (pin "3") (pinfunction "3_3") (pintype "passive"))
    )
    (net (code "51") (name "Net-(IC5-QA)") (class "Default")
      (node (ref "IC5") (pin "15") (pinfunction "QA_15") (pintype "tri_state"))
      (node (ref "RN2") (pin "8") (pinfunction "2_8") (pintype "passive"))
    )
    (net (code "52") (name "Net-(IC5-QB)") (class "Default")
      (node (ref "IC5") (pin "1") (pinfunction "QB_1") (pintype "tri_state"))
      (node (ref "RN2") (pin "7") (pinfunction "2_7") (pintype "passive"))
    )
    (net (code "53") (name "Net-(IC5-QC)") (class "Default")
      (node (ref "IC5") (pin "2") (pinfunction "QC_2") (pintype "tri_state"))
      (node (ref "RN2") (pin "6") (pinfunction "2_6") (pintype "passive"))
    )
    (net (code "54") (name "Net-(IC5-QD)") (class "Default")
      (node (ref "IC5") (pin "3") (pinfunction "QD_3") (pintype "tri_state"))
      (node (ref "RN2") (pin "5") (pinfunction "2_5") (pintype "passive"))
    )
    (net (code "55") (name "Net-(IC5-QE)") (class "Default")
      (node (ref "IC5") (pin "4") (pinfunction "QE_4") (pintype "tri_state"))
      (node (ref "RN3") (pin "8") (pinfunction "2_8") (pintype "passive"))
    )
    (net (code "56") (name "Net-(IC5-QF)") (class "Default")
      (node (ref "IC5") (pin "5") (pinfunction "QF_5") (pintype "tri_state"))
      (node (ref "RN3") (pin "7") (pinfunction "2_7") (pintype "passive"))
    )
    (net (code "57") (name "Net-(IC5-QG)") (class "Default")
      (node (ref "IC5") (pin "6") (pinfunction "QG_6") (pintype "tri_state"))
      (node (ref "RN3") (pin "6") (pinfunction "2_6") (pintype "passive"))
    )
    (net (code "58") (name "Net-(IC5-QH)") (class "Default")
      (node (ref "IC5") (pin "7") (pinfunction "QH_7") (pintype "tri_state"))
      (node (ref "RN3") (pin "5") (pinfunction "2_5") (pintype "passive"))
    )
    (net (code "59") (name "Net-(IC6-LEDA)") (class "Default")
      (node (ref "IC6") (pin "27") (pinfunction "LEDA_27") (pintype "bidirectional"))
      (node (ref "R1") (pin "1") (pinfunction "1_1") (pintype "passive"))
    )
    (net (code "60") (name "Net-(IC6-LEDB)") (class "Default")
      (node (ref "IC6") (pin "26") (pinfunction "LEDB_26") (pintype "bidirectional"))
      (node (ref "R2") (pin "1") (pinfunction "1_1") (pintype "passive"))
    )
    (net (code "61") (name "Net-(IC6-OSC1)") (class "Default")
      (node (ref "CX2") (pin "1") (pinfunction "1_1") (pintype "passive"))
      (node (ref "IC6") (pin "23") (pinfunction "OSC1_23") (pintype "bidirectional"))
      (node (ref "X2") (pin "2") (pinfunction "2_2") (pintype "passive"))
      (node (ref "X2A") (pin "1") (pinfunction "1_1") (pintype "passive"))
    )
    (net (code "62") (name "Net-(IC6-OSC2)") (class "Default")
      (node (ref "CX1") (pin "1") (pinfunction "1_1") (pintype "passive"))
      (node (ref "IC6") (pin "24") (pinfunction "OSC2_24") (pintype "bidirectional"))
      (node (ref "X2") (pin "1") (pinfunction "1_1") (pintype "passive"))
      (node (ref "X2A") (pin "2") (pinfunction "2_2") (pintype "passive"))
    )
    (net (code "63") (name "Net-(IC6-RBIAS)") (class "Default")
      (node (ref "IC6") (pin "14") (pinfunction "RBIAS_14") (pintype "bidirectional"))
      (node (ref "RBS") (pin "2") (pinfunction "2_2") (pintype "passive"))
    )
    (net (code "64") (name "Net-(IC6-VCAP)") (class "Default")
      (node (ref "CAP") (pin "1") (pinfunction "1_1") (pintype "passive"))
      (node (ref "IC6") (pin "1") (pinfunction "VCAP_1") (pintype "bidirectional"))
    )
    (net (code "65") (name "Net-(IC7-PB5(NRES))") (class "Default")
      (node (ref "IC7") (pin "1") (pinfunction "PB5(NRES)_1") (pintype "bidirectional"))
      (node (ref "S1") (pin "2") (pinfunction "P_2") (pintype "passive"))
    )
    (net (code "66") (name "Net-(J2-P)") (class "Default")
      (node (ref "J0") (pin "2") (pinfunction "2_2") (pintype "passive"))
      (node (ref "J2") (pin "2") (pinfunction "P_2") (pintype "passive"))
    )
    (net (code "67") (name "Net-(J2-S)") (class "Default")
      (node (ref "J2") (pin "3") (pinfunction "S_3") (pintype "passive"))
      (node (ref "PTC") (pin "P$1") (pinfunction "1_P$1") (pintype "bidirectional"))
    )
    (net (code "68") (name "Net-(LCD-K)") (class "Default")
      (node (ref "LCD") (pin "16") (pinfunction "K_16") (pintype "input"))
      (node (ref "LCD") (pin "3") (pinfunction "VO_3") (pintype "input"))
      (node (ref "RLCD") (pin "1") (pinfunction "1_1") (pintype "passive"))
    )
    (net (code "69") (name "Net-(RD+-Pad2)") (class "Default")
      (node (ref "RD+") (pin "2") (pinfunction "2_2") (pintype "passive"))
      (node (ref "USB") (pin "D+") (pinfunction "D+_D+") (pintype "bidirectional"))
    )
    (net (code "70") (name "Net-(RD--Pad2)") (class "Default")
      (node (ref "RD-") (pin "2") (pinfunction "2_2") (pintype "passive"))
      (node (ref "RUSB") (pin "1") (pinfunction "1_1") (pintype "passive"))
      (node (ref "USB") (pin "D-") (pinfunction "D-_D-") (pintype "bidirectional"))
    )
    (net (code "71") (name "Net-(RN2B-1)") (class "Default")
      (node (ref "RN2") (pin "2") (pinfunction "1_2") (pintype "passive"))
      (node (ref "T2") (pin "3") (pinfunction "G_3") (pintype "bidirectional"))
    )
    (net (code "72") (name "Net-(RN2C-1)") (class "Default")
      (node (ref "RN2") (pin "3") (pinfunction "1_3") (pintype "passive"))
      (node (ref "T3") (pin "3") (pinfunction "G_3") (pintype "bidirectional"))
    )
    (net (code "73") (name "Net-(RN2D-1)") (class "Default")
      (node (ref "RN2") (pin "4") (pinfunction "1_4") (pintype "passive"))
      (node (ref "T4") (pin "3") (pinfunction "G_3") (pintype "bidirectional"))
    )
    (net (code "74") (name "Net-(RN3B-1)") (class "Default")
      (node (ref "RN3") (pin "2") (pinfunction "1_2") (pintype "passive"))
      (node (ref "T6") (pin "3") (pinfunction "G_3") (pintype "bidirectional"))
    )
    (net (code "75") (name "Net-(RN3C-1)") (class "Default")
      (node (ref "RN3") (pin "3") (pinfunction "1_3") (pintype "passive"))
      (node (ref "T7") (pin "3") (pinfunction "G_3") (pintype "bidirectional"))
    )
    (net (code "76") (name "Net-(RN3D-1)") (class "Default")
      (node (ref "RN3") (pin "4") (pinfunction "1_4") (pintype "passive"))
      (node (ref "T8") (pin "3") (pinfunction "G_3") (pintype "bidirectional"))
    )
    (net (code "77") (name "Net-(RN4C-2)") (class "Default")
      (node (ref "C7") (pin "2") (pinfunction "2_2") (pintype "passive"))
      (node (ref "RN4") (pin "5") (pinfunction "2_5") (pintype "passive"))
      (node (ref "RN4") (pin "6") (pinfunction "2_6") (pintype "passive"))
    )
    (net (code "78") (name "Net-(S1-O)") (class "Default")
      (node (ref "ISP") (pin "5") (pinfunction "5_5") (pintype "passive"))
      (node (ref "S1") (pin "1") (pinfunction "O_1") (pintype "passive"))
    )
    (net (code "79") (name "Net-(T1-G)") (class "Default")
      (node (ref "RN2") (pin "1") (pinfunction "1_1") (pintype "passive"))
      (node (ref "T1") (pin "3") (pinfunction "G_3") (pintype "bidirectional"))
    )
    (net (code "80") (name "Net-(T1-M2)") (class "Default")
      (node (ref "S12") (pin "1") (pinfunction "1_1") (pintype "passive"))
      (node (ref "T1") (pin "4") (pinfunction "M2_4") (pintype "bidirectional"))
      (node (ref "V1") (pin "2") (pinfunction "2_2") (pintype "passive"))
    )
    (net (code "81") (name "Net-(T2-M2)") (class "Default")
      (node (ref "S12") (pin "2") (pinfunction "2_2") (pintype "passive"))
      (node (ref "T2") (pin "4") (pinfunction "M2_4") (pintype "bidirectional"))
      (node (ref "V2") (pin "2") (pinfunction "2_2") (pintype "passive"))
    )
    (net (code "82") (name "Net-(T3-M2)") (class "Default")
      (node (ref "S34") (pin "1") (pinfunction "1_1") (pintype "passive"))
      (node (ref "T3") (pin "4") (pinfunction "M2_4") (pintype "bidirectional"))
      (node (ref "V3") (pin "2") (pinfunction "2_2") (pintype "passive"))
    )
    (net (code "83") (name "Net-(T4-M2)") (class "Default")
      (node (ref "S34") (pin "2") (pinfunction "2_2") (pintype "passive"))
      (node (ref "T4") (pin "4") (pinfunction "M2_4") (pintype "bidirectional"))
      (node (ref "V4") (pin "2") (pinfunction "2_2") (pintype "passive"))
    )
    (net (code "84") (name "Net-(T5-G)") (class "Default")
      (node (ref "RN3") (pin "1") (pinfunction "1_1") (pintype "passive"))
      (node (ref "T5") (pin "3") (pinfunction "G_3") (pintype "bidirectional"))
    )
    (net (code "85") (name "Net-(T5-M2)") (class "Default")
      (node (ref "S56") (pin "1") (pinfunction "1_1") (pintype "passive"))
      (node (ref "T5") (pin "4") (pinfunction "M2_4") (pintype "bidirectional"))
      (node (ref "V5") (pin "2") (pinfunction "2_2") (pintype "passive"))
    )
    (net (code "86") (name "Net-(T6-M2)") (class "Default")
      (node (ref "S56") (pin "2") (pinfunction "2_2") (pintype "passive"))
      (node (ref "T6") (pin "4") (pinfunction "M2_4") (pintype "bidirectional"))
      (node (ref "V6") (pin "2") (pinfunction "2_2") (pintype "passive"))
    )
    (net (code "87") (name "Net-(T7-M2)") (class "Default")
      (node (ref "S78") (pin "1") (pinfunction "1_1") (pintype "passive"))
      (node (ref "T7") (pin "4") (pinfunction "M2_4") (pintype "bidirectional"))
      (node (ref "V7") (pin "2") (pinfunction "2_2") (pintype "passive"))
    )
    (net (code "88") (name "Net-(T8-M2)") (class "Default")
      (node (ref "S78") (pin "2") (pinfunction "2_2") (pintype "passive"))
      (node (ref "T8") (pin "4") (pinfunction "M2_4") (pintype "bidirectional"))
      (node (ref "V8") (pin "2") (pinfunction "2_2") (pintype "passive"))
    )
    (net (code "89") (name "VCC") (class "Default")
      (node (ref "C3") (pin "+") (pinfunction "+_+") (pintype "passive"))
      (node (ref "C4") (pin "1") (pinfunction "1_1") (pintype "passive"))
      (node (ref "EXTIN") (pin "1") (pinfunction "1_1") (pintype "passive"))
      (node (ref "EXTOUT") (pin "1") (pinfunction "1_1") (pintype "passive"))
      (node (ref "IC2") (pin "2") (pinfunction "OUT_2") (pintype "passive"))
      (node (ref "IC4") (pin "18") (pinfunction "AVCC_18") (pintype "power_in"))
      (node (ref "IC4") (pin "4") (pinfunction "VCC_4") (pintype "power_in"))
      (node (ref "IC4") (pin "6") (pinfunction "VCC_6") (pintype "power_in"))
      (node (ref "IC5") (pin "10") (pinfunction "SCL_10") (pintype "input"))
      (node (ref "IC5") (pin "16") (pinfunction "VCC_16") (pintype "power_in"))
      (node (ref "IC6") (pin "15") (pinfunction "VDDTX_15") (pintype "bidirectional"))
      (node (ref "IC6") (pin "19") (pinfunction "VDDRX_19") (pintype "bidirectional"))
      (node (ref "IC6") (pin "20") (pinfunction "VDDPLL_20") (pintype "bidirectional"))
      (node (ref "IC6") (pin "25") (pinfunction "VDDOSC_25") (pintype "bidirectional"))
      (node (ref "IC6") (pin "28") (pinfunction "VDD_28") (pintype "bidirectional"))
      (node (ref "IC7") (pin "8") (pinfunction "VCC_8") (pintype "bidirectional"))
      (node (ref "IC8") (pin "VDD") (pinfunction "VCC_VDD") (pintype "power_in"))
      (node (ref "IC9") (pin "8") (pinfunction "VCC_8") (pintype "power_in"))
      (node (ref "JP1") (pin "3") (pinfunction "3_3") (pintype "passive"))
      (node (ref "L2") (pin "2") (pinfunction "2_2") (pintype "passive"))
      (node (ref "RN1") (pin "1") (pinfunction "1_1") (pintype "passive"))
      (node (ref "ROE") (pin "2") (pinfunction "2_2") (pintype "passive"))
      (node (ref "RRST") (pin "1") (pinfunction "1_1") (pintype "passive"))
      (node (ref "RUSB") (pin "2") (pinfunction "2_2") (pintype "passive"))
    )
    (net (code "90") (name "unconnected-(IC3-SQW{slash}OUT-Pad7)") (class "Default")
      (node (ref "IC3") (pin "7") (pinfunction "SQW/OUT_7") (pintype "bidirectional"))
    )
    (net (code "91") (name "unconnected-(IC6-CLKOUT-Pad3)") (class "Default")
      (node (ref "IC6") (pin "3") (pinfunction "CLKOUT_3") (pintype "bidirectional"))
    )
    (net (code "92") (name "unconnected-(IC6-NC-Pad5)") (class "Default")
      (node (ref "IC6") (pin "5") (pinfunction "NC_5") (pintype "bidirectional"))
    )
    (net (code "93") (name "unconnected-(IC6-{slash}INT-Pad4)") (class "Default")
      (node (ref "IC6") (pin "4") (pinfunction "/INT_4") (pintype "bidirectional"))
    )
    (net (code "94") (name "unconnected-(IC8-PadANT)") (class "Default")
      (node (ref "IC8") (pin "ANT") (pinfunction "ANT_ANT") (pintype "passive"))
    )
    (net (code "95") (name "unconnected-(IC8-PadFFS)") (class "Default")
      (node (ref "IC8") (pin "FFS") (pinfunction "FFS_FFS") (pintype "bidirectional"))
    )
    (net (code "96") (name "unconnected-(J2-O-Pad1)") (class "Default")
      (node (ref "J2") (pin "1") (pinfunction "O_1") (pintype "passive"))
    )
    (net (code "97") (name "unconnected-(LCD-DB0-Pad7)") (class "Default")
      (node (ref "LCD") (pin "7") (pinfunction "DB0_7") (pintype "bidirectional"))
    )
    (net (code "98") (name "unconnected-(LCD-DB1-Pad8)") (class "Default")
      (node (ref "LCD") (pin "8") (pinfunction "DB1_8") (pintype "bidirectional"))
    )
    (net (code "99") (name "unconnected-(LCD-DB2-Pad9)") (class "Default")
      (node (ref "LCD") (pin "9") (pinfunction "DB2_9") (pintype "bidirectional"))
    )
    (net (code "100") (name "unconnected-(LCD-DB3-Pad10)") (class "Default")
      (node (ref "LCD") (pin "10") (pinfunction "DB3_10") (pintype "bidirectional"))
    )
    (net (code "101") (name "unconnected-(RJ1-PadNC)") (class "Default")
      (node (ref "RJ1") (pin "NC") (pinfunction "NC_NC") (pintype "bidirectional"))
    )
    (net (code "102") (name "unconnected-(RJ1-PadP5)") (class "Default")
      (node (ref "RJ1") (pin "P5") (pinfunction "P5_P5") (pintype "bidirectional"))
    )
  )
)
